# Sheet1.net
KiCad netlist of a schematic drawn in Altium Designer
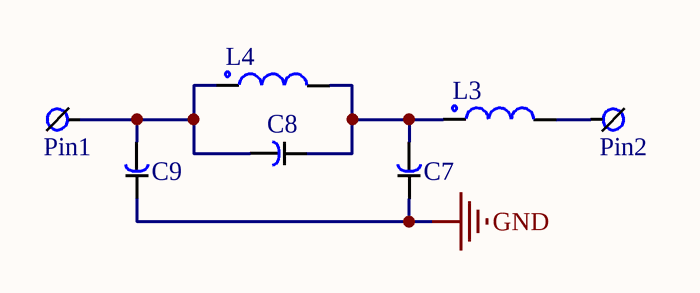
[diagram p0: Sheet1.SchDoc]

(export (version "E")
  (design (tool "Eeschema 10.0.6"))
  (components
    (comp (ref "C7") (value "C7") (footprint "C7(1206)") (libsource (lib "Schlib") (part "C7")))
    (comp (ref "C8") (value "C8") (footprint "C8(1812)") (libsource (lib "Schlib") (part "C8")))
    (comp (ref "C9") (value "C9") (footprint "C9(1812)") (libsource (lib "Schlib") (part "C9")))
    (comp (ref "L3") (value "L") (footprint "L3,L4") (libsource (lib "Schlib") (part "L")))
    (comp (ref "L4") (value "L") (footprint "L3,L4") (libsource (lib "Schlib") (part "L")))
    (comp (ref "Pin1") (value "Pin") (footprint "Pin") (libsource (lib "Schlib") (part "Pin")))
    (comp (ref "Pin2") (value "Pin") (footprint "Pin") (libsource (lib "Schlib") (part "Pin")))
  )
  (nets
    (net (code "1") (name "GND") (class "Default")
      (node (ref "C7") (pin "2") (pinfunction "2_2") (pintype "passive"))
      (node (ref "C9") (pin "2") (pinfunction "2_2") (pintype "passive"))
    )
    (net (code "2") (name "Net-(C7-Pad1)") (class "Default")
      (node (ref "C7") (pin "1") (pinfunction "1_1") (pintype "passive"))
      (node (ref "C8") (pin "2") (pinfunction "2_2") (pintype "passive"))
      (node (ref "L3") (pin "1") (pinfunction "1_1") (pintype "passive"))
      (node (ref "L4") (pin "2") (pinfunction "2_2") (pintype "passive"))
    )
    (net (code "3") (name "Net-(Pin1-4)") (class "Default")
      (node (ref "C8") (pin "1") (pinfunction "1_1") (pintype "passive"))
      (node (ref "C9") (pin "1") (pinfunction "1_1") (pintype "passive"))
      (node (ref "L4") (pin "1") (pinfunction "1_1") (pintype "passive"))
      (node (ref "Pin1") (pin "1") (pinfunction "4_1") (pintype "passive"))
    )
    (net (code "4") (name "Net-(Pin2-4)") (class "Default")
      (node (ref "L3") (pin "2") (pinfunction "2_2") (pintype "passive"))
      (node (ref "Pin2") (pin "1") (pinfunction "4_1") (pintype "passive"))
    )
  )
)
